# Ethernet_Sheet.net
KiCad netlist of a schematic drawn in Altium Designer
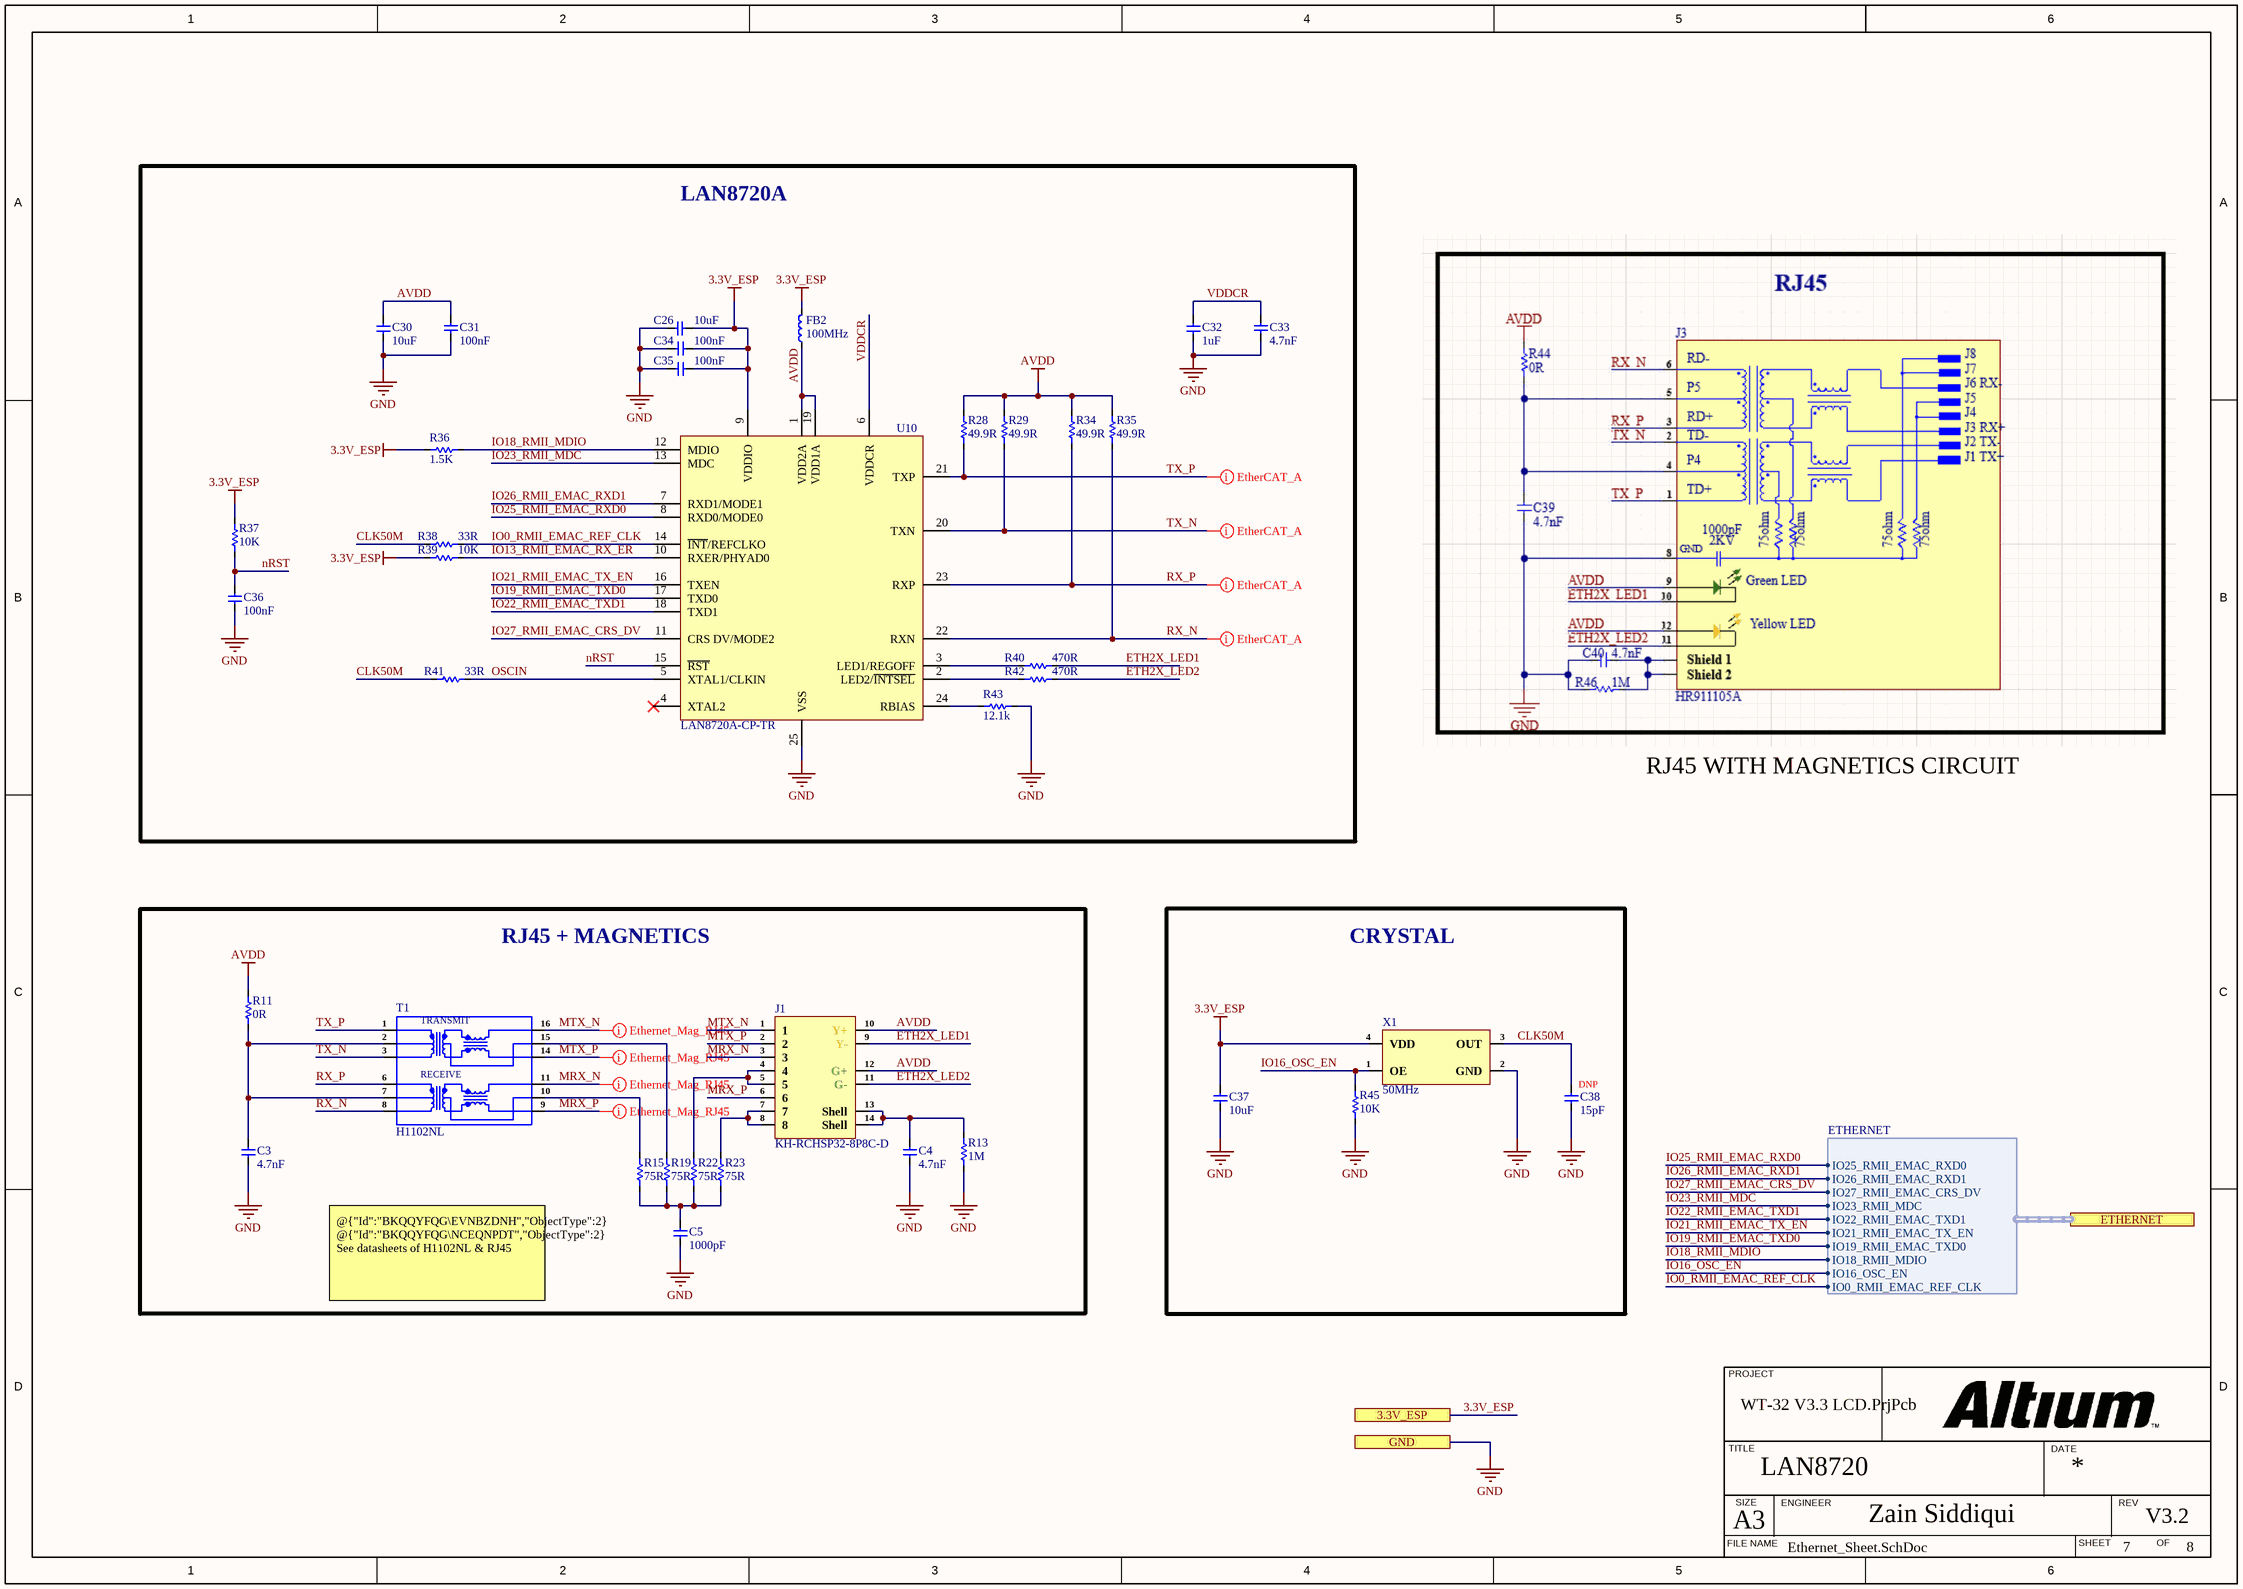
[diagram p0: Ethernet_Sheet.SchDoc]

(export (version "E")
  (design (tool "Eeschema 10.0.6"))
  (components
    (comp (ref "C3")
      (value "4.7nF")
      (footprint "Cap-0402")
      (description "CAP CER 4700PF 50V X7R 0402")
      (fields
        (field (name "MANUFACTURER") "Yageo")
        (field (name "MANUFACTURER PART NUMBER") "CC0402KRX7R9BB472")
      )
      (libsource (lib "eSpark Libraries") (part "CC0402KRX7R9BB472"))
    )
    (comp (ref "C4")
      (value "4.7nF")
      (footprint "Cap-1206")
      (description "CAP CER 4700PF 1KV X7R 1206")
      (fields
        (field (name "MANUFACTURER") "Yageo")
        (field (name "MANUFACTURER PART NUMBER") "CC1206KKX7RCBB472")
      )
      (libsource (lib "eSpark Libraries") (part "CC1206KKX7RCBB472"))
    )
    (comp (ref "C5")
      (value "1000pF")
      (footprint "Cap-1206")
      (description "CAP CER 1000PF 2KV X7R 1206")
      (fields
        (field (name "MANUFACTURER") "Yageo")
        (field (name "MANUFACTURER PART NUMBER") "CC1206KKX7RDBB102")
      )
      (libsource (lib "eSpark Libraries") (part "CC1206KKX7RDBB102"))
    )
    (comp (ref "C26")
      (value "10uF")
      (footprint "Cap-0603")
      (description "CAP CER 10UF 25V X5R 0603")
      (fields
        (field (name "MANUFACTURER") "Samsung")
        (field (name "MANUFACTURER PART NUMBER") "CL10A106MA8NRNC")
      )
      (libsource (lib "eSpark Libraries") (part "CL10A106MA8NRNC"))
    )
    (comp (ref "C30")
      (value "10uF")
      (footprint "Cap-0603")
      (description "CAP CER 10UF 25V X5R 0603")
      (fields
        (field (name "MANUFACTURER") "Samsung")
        (field (name "MANUFACTURER PART NUMBER") "CL10A106MA8NRNC")
      )
      (libsource (lib "eSpark Libraries") (part "CL10A106MA8NRNC"))
    )
    (comp (ref "C31")
      (value "100nF")
      (footprint "cap-0402")
      (description "CAP CER 0.1UF 50V X7R 0402")
      (fields
        (field (name "MANUFACTURER") "TDK")
        (field (name "MANUFACTURER PART NUMBER") "C1005X7R1H104KT000F")
      )
      (libsource (lib "eSpark Libraries") (part "C1005X7R1H104KT000F"))
    )
    (comp (ref "C32")
      (value "1uF")
      (footprint "Cap-0402")
      (description "CAP CER 1UF 16V X5R 0402")
      (fields
        (field (name "MANUFACTURER") "Yageo")
        (field (name "MANUFACTURER PART NUMBER") "CC0402KRX5R7BB105")
      )
      (libsource (lib "eSpark Libraries") (part "CC0402KRX5R7BB105"))
    )
    (comp (ref "C33")
      (value "4.7nF")
      (footprint "Cap-0402")
      (description "CAP CER 4700PF 50V X7R 0402")
      (fields
        (field (name "MANUFACTURER") "Yageo")
        (field (name "MANUFACTURER PART NUMBER") "CC0402KRX7R9BB472")
      )
      (libsource (lib "eSpark Libraries") (part "CC0402KRX7R9BB472"))
    )
    (comp (ref "C34")
      (value "100nF")
      (footprint "cap-0402")
      (description "CAP CER 0.1UF 50V X7R 0402")
      (fields
        (field (name "MANUFACTURER") "TDK")
        (field (name "MANUFACTURER PART NUMBER") "C1005X7R1H104KT000F")
      )
      (libsource (lib "eSpark Libraries") (part "C1005X7R1H104KT000F"))
    )
    (comp (ref "C35")
      (value "100nF")
      (footprint "cap-0402")
      (description "CAP CER 0.1UF 50V X7R 0402")
      (fields
        (field (name "MANUFACTURER") "TDK")
        (field (name "MANUFACTURER PART NUMBER") "C1005X7R1H104KT000F")
      )
      (libsource (lib "eSpark Libraries") (part "C1005X7R1H104KT000F"))
    )
    (comp (ref "C36")
      (value "100nF")
      (footprint "cap-0402")
      (description "CAP CER 0.1UF 50V X7R 0402")
      (fields
        (field (name "MANUFACTURER") "TDK")
        (field (name "MANUFACTURER PART NUMBER") "C1005X7R1H104KT000F")
      )
      (libsource (lib "eSpark Libraries") (part "C1005X7R1H104KT000F"))
    )
    (comp (ref "C37")
      (value "10uF")
      (footprint "Cap-0603")
      (description "CAP CER 10UF 25V X5R 0603")
      (fields
        (field (name "MANUFACTURER") "Samsung")
        (field (name "MANUFACTURER PART NUMBER") "CL10A106MA8NRNC")
      )
      (libsource (lib "eSpark Libraries") (part "CL10A106MA8NRNC"))
    )
    (comp (ref "C38")
      (value "15pF")
      (footprint "Cap-0603")
      (description "CAP CER 15PF 50V C0G/NPO 0603")
      (fields
        (field (name "MANUFACTURER") "Yageo")
        (field (name "MANUFACTURER PART NUMBER") "CC0603JRNPO9BN150")
      )
      (libsource (lib "eSpark Libraries") (part "CC0603JRNPO9BN150"))
    )
    (comp (ref "FB2")
      (value "100MHz")
      (footprint "IND-1206")
      (description "FERRITE BEAD 120 OHM 1206 1LN")
      (fields
        (field (name "MANUFACTURER") "Murata")
        (field (name "MANUFACTURER PART NUMBER") "BLM31PG121SN1L")
      )
      (libsource (lib "eSpark Libraries") (part "BLM31PG121SN1L"))
    )
    (comp (ref "J1")
      (value "KH-RCHSP32-8P8C-D")
      (footprint "KH-RCHSP32-8P8C-D")
      (description "Jack Modular Connector RJ45 Through Hole, Right Angle Shielded")
      (fields (field (name "MANUFACTURER") "kinghelm") (field (name "LCSC PART NUMBER") "C2828084"))
      (libsource (lib "eSpark Libraries") (part "KH-RCHSP32-8P8C-D"))
    )
    (comp (ref "R11")
      (value "0R")
      (footprint "Res-0402")
      (description "RES 0 OHM JUMPER 1/16W 0402")
      (fields
        (field (name "MANUFACTURER") "Yageo")
        (field (name "MANUFACTURER PART NUMBER") "RC0402FR-070RL")
      )
      (libsource (lib "eSpark Libraries") (part "RC0402FR-070RL"))
    )
    (comp (ref "R13")
      (value "1M")
      (footprint "Res-1206")
      (description "RES 1M OHM 1% 1/4W 1206")
      (fields
        (field (name "MANUFACTURER") "Yageo")
        (field (name "MANUFACTURER PART NUMBER") "RC1206FR-071ML")
      )
      (libsource (lib "eSpark Libraries") (part "RC1206FR-071ML"))
    )
    (comp (ref "R15")
      (value "75R")
      (footprint "Res-0402")
      (description "75Ω ±1% 62.5mW 0402 Thick Film Resistor")
      (fields
        (field (name "MANUFACTURER") "YAGEO")
        (field (name "MANUFACTURER PART NUMBER") "RC0402FR-0775RL")
      )
      (libsource (lib "eSpark Libraries") (part "RC0402FR-0775RL"))
    )
    (comp (ref "R19")
      (value "75R")
      (footprint "Res-0402")
      (description "75Ω ±1% 62.5mW 0402 Thick Film Resistor")
      (fields
        (field (name "MANUFACTURER") "YAGEO")
        (field (name "MANUFACTURER PART NUMBER") "RC0402FR-0775RL")
      )
      (libsource (lib "eSpark Libraries") (part "RC0402FR-0775RL"))
    )
    (comp (ref "R22")
      (value "75R")
      (footprint "Res-0402")
      (description "75Ω ±1% 62.5mW 0402 Thick Film Resistor")
      (fields
        (field (name "MANUFACTURER") "YAGEO")
        (field (name "MANUFACTURER PART NUMBER") "RC0402FR-0775RL")
      )
      (libsource (lib "eSpark Libraries") (part "RC0402FR-0775RL"))
    )
    (comp (ref "R23")
      (value "75R")
      (footprint "Res-0402")
      (description "75Ω ±1% 62.5mW 0402 Thick Film Resistor")
      (fields
        (field (name "MANUFACTURER") "YAGEO")
        (field (name "MANUFACTURER PART NUMBER") "RC0402FR-0775RL")
      )
      (libsource (lib "eSpark Libraries") (part "RC0402FR-0775RL"))
    )
    (comp (ref "R28")
      (value "49.9R")
      (footprint "Res-0402")
      (description "49.9Ω 62.5mW 50V ±100ppm/℃ Thick Film Resistor ±1% 0402 Chip Resistor - Surface Mount ROHS")
      (fields
        (field (name "MANUFACTURER") "YAGEO")
        (field (name "MANUFACTURER PART NUMBER") "RC0402FR-0749R9L")
      )
      (libsource (lib "eSpark Libraries") (part "RC0402FR-0749R9L"))
    )
    (comp (ref "R29")
      (value "49.9R")
      (footprint "Res-0402")
      (description "49.9Ω 62.5mW 50V ±100ppm/℃ Thick Film Resistor ±1% 0402 Chip Resistor - Surface Mount ROHS")
      (fields
        (field (name "MANUFACTURER") "YAGEO")
        (field (name "MANUFACTURER PART NUMBER") "RC0402FR-0749R9L")
      )
      (libsource (lib "eSpark Libraries") (part "RC0402FR-0749R9L"))
    )
    (comp (ref "R34")
      (value "49.9R")
      (footprint "Res-0402")
      (description "49.9Ω 62.5mW 50V ±100ppm/℃ Thick Film Resistor ±1% 0402 Chip Resistor - Surface Mount ROHS")
      (fields
        (field (name "MANUFACTURER") "YAGEO")
        (field (name "MANUFACTURER PART NUMBER") "RC0402FR-0749R9L")
      )
      (libsource (lib "eSpark Libraries") (part "RC0402FR-0749R9L"))
    )
    (comp (ref "R35")
      (value "49.9R")
      (footprint "Res-0402")
      (description "49.9Ω 62.5mW 50V ±100ppm/℃ Thick Film Resistor ±1% 0402 Chip Resistor - Surface Mount ROHS")
      (fields
        (field (name "MANUFACTURER") "YAGEO")
        (field (name "MANUFACTURER PART NUMBER") "RC0402FR-0749R9L")
      )
      (libsource (lib "eSpark Libraries") (part "RC0402FR-0749R9L"))
    )
    (comp (ref "R36")
      (value "1.5K")
      (footprint "Res-0402")
      (description "RES 1.5K OHM 1% 1/16W 0402")
      (fields
        (field (name "MANUFACTURER") "Yageo")
        (field (name "MANUFACTURER PART NUMBER") "RC0402FR-071K5L")
      )
      (libsource (lib "eSpark Libraries") (part "RC0402FR-071K5L"))
    )
    (comp (ref "R37")
      (value "10K")
      (footprint "Res-0402")
      (description "RES 10K OHM 1% 1/16W 0402")
      (fields
        (field (name "MANUFACTURER") "Yageo")
        (field (name "MANUFACTURER PART NUMBER") "RC0402FR-0710KL")
      )
      (libsource (lib "eSpark Libraries") (part "RC0402FR-0710KL"))
    )
    (comp (ref "R38")
      (value "33R")
      (footprint "Res-0402")
      (description "RES 33 OHM 1% 1/16W 0402")
      (fields
        (field (name "MANUFACTURER") "Yageo")
        (field (name "MANUFACTURER PART NUMBER") "RC0402FR-0733RL")
      )
      (libsource (lib "eSpark Libraries") (part "RC0402FR-0733RL"))
    )
    (comp (ref "R39")
      (value "10K")
      (footprint "Res-0402")
      (description "RES 10K OHM 1% 1/16W 0402")
      (fields
        (field (name "MANUFACTURER") "Yageo")
        (field (name "MANUFACTURER PART NUMBER") "RC0402FR-0710KL")
      )
      (libsource (lib "eSpark Libraries") (part "RC0402FR-0710KL"))
    )
    (comp (ref "R40")
      (value "470R")
      (footprint "Res-0402")
      (description "RES 470 OHM 1% 1/16W 0402")
      (fields
        (field (name "MANUFACTURER") "Yageo")
        (field (name "MANUFACTURER PART NUMBER") "RC0402FR-07470RL")
      )
      (libsource (lib "eSpark Libraries") (part "RC0402FR-07470RL"))
    )
    (comp (ref "R41")
      (value "33R")
      (footprint "Res-0402")
      (description "RES 33 OHM 1% 1/16W 0402")
      (fields
        (field (name "MANUFACTURER") "Yageo")
        (field (name "MANUFACTURER PART NUMBER") "RC0402FR-0733RL")
      )
      (libsource (lib "eSpark Libraries") (part "RC0402FR-0733RL"))
    )
    (comp (ref "R42")
      (value "470R")
      (footprint "Res-0402")
      (description "RES 470 OHM 1% 1/16W 0402")
      (fields
        (field (name "MANUFACTURER") "Yageo")
        (field (name "MANUFACTURER PART NUMBER") "RC0402FR-07470RL")
      )
      (libsource (lib "eSpark Libraries") (part "RC0402FR-07470RL"))
    )
    (comp (ref "R43")
      (value "12.1k")
      (footprint "Res-0402")
      (description "RES SMD 12.1KOHM 0.1% 1/16W 0402")
      (fields
        (field (name "MANUFACTURER") "Yageo")
        (field (name "MANUFACTURER PART NUMBER") "RT0402BRD0712K1L")
      )
      (libsource (lib "eSpark Libraries") (part "RT0402BRD0712K1L"))
    )
    (comp (ref "R45")
      (value "10K")
      (footprint "Res-0402")
      (description "RES 10K OHM 1% 1/16W 0402")
      (fields
        (field (name "MANUFACTURER") "Yageo")
        (field (name "MANUFACTURER PART NUMBER") "RC0402FR-0710KL")
      )
      (libsource (lib "eSpark Libraries") (part "RC0402FR-0710KL"))
    )
    (comp (ref "T1")
      (value "H1102NL")
      (footprint "H1102NLT")
      (description "XFRMR MAGNETIC 1PORT 1:1 10/100")
      (fields (field (name "MANUFACTURER") "Pulse") (field (name "LCSC PART NUMBER") "C18584"))
      (libsource (lib "eSpark Libraries") (part "H1102NL"))
    )
    (comp (ref "U10")
      (value "LAN8720A-CP-TR")
      (footprint "LAN8720A-CP-TR")
      (description "IC TRANSCEIVER FULL 2/2 24SQFN")
      (fields (field (name "MANUFACTURER") "MICROCHIP") (field (name "LCSC PART NUMBER") "C45223"))
      (libsource (lib "eSpark Libraries") (part "LAN8720A-CP-TR"))
    )
    (comp (ref "X1")
      (value "50MHz")
      (footprint "OT2EL4C4JI-111OLP-50M")
      (description "1.8V~3.3V ±10ppm ±20ppm CMOS 50MHz SMD3225-4P Crystal Oscillators ROHS")
      (fields
        (field (name "MANUFACTURER") "YXC Crystal Oscillators")
        (field (name "MANUFACTURER PART NUMBER") "OT2EL4C4JI-111OLP-50M")
      )
      (libsource (lib "eSpark Libraries") (part "OT2EL4C4JI-111OLP-50M"))
    )
  )
  (nets
    (net (code "2") (name "/CLK50M") (class "Default")
      (node (ref "C38") (pin "2") (pinfunction "2_2") (pintype "passive"))
      (node (ref "R38") (pin "1") (pinfunction "1_1") (pintype "passive"))
      (node (ref "R41") (pin "1") (pinfunction "1_1") (pintype "passive"))
      (node (ref "X1") (pin "3") (pinfunction "OUT_3") (pintype "passive"))
    )
    (net (code "3") (name "/ETH2X_LED1") (class "Default")
      (node (ref "J1") (pin "9") (pinfunction "Y-_9") (pintype "passive"))
      (node (ref "R40") (pin "2") (pinfunction "2_2") (pintype "passive"))
    )
    (net (code "4") (name "/ETH2X_LED2") (class "Default")
      (node (ref "J1") (pin "11") (pinfunction "G-_11") (pintype "passive"))
      (node (ref "R42") (pin "2") (pinfunction "2_2") (pintype "passive"))
    )
    (net (code "5") (name "/IO0_RMII_EMAC_REF_CLK") (class "Default")
      (node (ref "R38") (pin "2") (pinfunction "2_2") (pintype "passive"))
      (node (ref "U10") (pin "14") (pinfunction "~{INT}/REFCLKO_14") (pintype "passive"))
    )
    (net (code "6") (name "/IO13_RMII_EMAC_RX_ER") (class "Default")
      (node (ref "R39") (pin "1") (pinfunction "1_1") (pintype "passive"))
      (node (ref "U10") (pin "10") (pinfunction "RXER/PHYAD0_10") (pintype "passive"))
    )
    (net (code "7") (name "/IO16_OSC_EN") (class "Default")
      (node (ref "R45") (pin "1") (pinfunction "1_1") (pintype "passive"))
      (node (ref "X1") (pin "1") (pinfunction "OE_1") (pintype "passive"))
    )
    (net (code "8") (name "/IO18_RMII_MDIO") (class "Default")
      (node (ref "R36") (pin "1") (pinfunction "1_1") (pintype "passive"))
      (node (ref "U10") (pin "12") (pinfunction "MDIO_12") (pintype "passive"))
    )
    (net (code "9") (name "/IO19_RMII_EMAC_TXD0") (class "Default")
      (node (ref "U10") (pin "17") (pinfunction "TXD0_17") (pintype "passive"))
    )
    (net (code "10") (name "/IO21_RMII_EMAC_TX_EN") (class "Default")
      (node (ref "U10") (pin "16") (pinfunction "TXEN_16") (pintype "passive"))
    )
    (net (code "11") (name "/IO22_RMII_EMAC_TXD1") (class "Default")
      (node (ref "U10") (pin "18") (pinfunction "TXD1_18") (pintype "passive"))
    )
    (net (code "12") (name "/IO23_RMII_MDC") (class "Default")
      (node (ref "U10") (pin "13") (pinfunction "MDC_13") (pintype "passive"))
    )
    (net (code "13") (name "/IO25_RMII_EMAC_RXD0") (class "Default")
      (node (ref "U10") (pin "8") (pinfunction "RXD0/MODE0_8") (pintype "passive"))
    )
    (net (code "14") (name "/IO26_RMII_EMAC_RXD1") (class "Default")
      (node (ref "U10") (pin "7") (pinfunction "RXD1/MODE1_7") (pintype "passive"))
    )
    (net (code "15") (name "/IO27_RMII_EMAC_CRS_DV") (class "Default")
      (node (ref "U10") (pin "11") (pinfunction "CRS_DV/MODE2_11") (pintype "passive"))
    )
    (net (code "16") (name "/MRX_N") (class "Default")
      (node (ref "J1") (pin "3") (pinfunction "3_3") (pintype "passive"))
      (node (ref "T1") (pin "11") (pinfunction "11_11") (pintype "passive"))
    )
    (net (code "17") (name "/MRX_P") (class "Default")
      (node (ref "J1") (pin "6") (pinfunction "6_6") (pintype "passive"))
      (node (ref "T1") (pin "9") (pinfunction "9_9") (pintype "passive"))
    )
    (net (code "18") (name "/MTX_N") (class "Default")
      (node (ref "J1") (pin "1") (pinfunction "1_1") (pintype "passive"))
      (node (ref "T1") (pin "16") (pinfunction "16_16") (pintype "passive"))
    )
    (net (code "19") (name "/MTX_P") (class "Default")
      (node (ref "J1") (pin "2") (pinfunction "2_2") (pintype "passive"))
      (node (ref "T1") (pin "14") (pinfunction "14_14") (pintype "passive"))
    )
    (net (code "20") (name "/OSCIN") (class "Default")
      (node (ref "R41") (pin "2") (pinfunction "2_2") (pintype "passive"))
      (node (ref "U10") (pin "5") (pinfunction "XTAL1/CLKIN_5") (pintype "passive"))
    )
    (net (code "21") (name "/RX_N") (class "Default")
      (node (ref "R35") (pin "1") (pinfunction "1_1") (pintype "passive"))
      (node (ref "T1") (pin "8") (pinfunction "8_8") (pintype "passive"))
      (node (ref "U10") (pin "22") (pinfunction "RXN_22") (pintype "passive"))
    )
    (net (code "22") (name "/RX_P") (class "Default")
      (node (ref "R34") (pin "1") (pinfunction "1_1") (pintype "passive"))
      (node (ref "T1") (pin "6") (pinfunction "6_6") (pintype "passive"))
      (node (ref "U10") (pin "23") (pinfunction "RXP_23") (pintype "passive"))
    )
    (net (code "23") (name "/TX_N") (class "Default")
      (node (ref "R29") (pin "1") (pinfunction "1_1") (pintype "passive"))
      (node (ref "T1") (pin "3") (pinfunction "3_3") (pintype "passive"))
      (node (ref "U10") (pin "20") (pinfunction "TXN_20") (pintype "passive"))
    )
    (net (code "24") (name "/TX_P") (class "Default")
      (node (ref "R28") (pin "1") (pinfunction "1_1") (pintype "passive"))
      (node (ref "T1") (pin "1") (pinfunction "1_1") (pintype "passive"))
      (node (ref "U10") (pin "21") (pinfunction "TXP_21") (pintype "passive"))
    )
    (net (code "25") (name "/VDDCR") (class "Default")
      (node (ref "C32") (pin "2") (pinfunction "2_2") (pintype "passive"))
      (node (ref "C33") (pin "1") (pinfunction "1_1") (pintype "passive"))
      (node (ref "U10") (pin "6") (pinfunction "VDDCR_6") (pintype "passive"))
    )
    (net (code "26") (name "/nRST") (class "Default")
      (node (ref "C36") (pin "2") (pinfunction "2_2") (pintype "passive"))
      (node (ref "R37") (pin "1") (pinfunction "1_1") (pintype "passive"))
      (node (ref "U10") (pin "15") (pinfunction "~{RST}_15") (pintype "passive"))
    )
    (net (code "28") (name "3.3V_ESP") (class "Default")
      (node (ref "C26") (pin "2") (pinfunction "2_2") (pintype "passive"))
      (node (ref "C34") (pin "1") (pinfunction "1_1") (pintype "passive"))
      (node (ref "C35") (pin "1") (pinfunction "1_1") (pintype "passive"))
      (node (ref "C37") (pin "2") (pinfunction "2_2") (pintype "passive"))
      (node (ref "FB2") (pin "2") (pinfunction "2_2") (pintype "passive"))
      (node (ref "R36") (pin "2") (pinfunction "2_2") (pintype "passive"))
      (node (ref "R37") (pin "2") (pinfunction "2_2") (pintype "passive"))
      (node (ref "R39") (pin "2") (pinfunction "2_2") (pintype "passive"))
      (node (ref "U10") (pin "9") (pinfunction "VDDIO_9") (pintype "passive"))
      (node (ref "X1") (pin "4") (pinfunction "VDD_4") (pintype "passive"))
    )
    (net (code "29") (name "AVDD") (class "Default")
      (node (ref "C30") (pin "2") (pinfunction "2_2") (pintype "passive"))
      (node (ref "C31") (pin "1") (pinfunction "1_1") (pintype "passive"))
      (node (ref "FB2") (pin "1") (pinfunction "1_1") (pintype "passive"))
      (node (ref "J1") (pin "10") (pinfunction "Y+_10") (pintype "passive"))
      (node (ref "J1") (pin "12") (pinfunction "G+_12") (pintype "passive"))
      (node (ref "R11") (pin "2") (pinfunction "2_2") (pintype "passive"))
      (node (ref "R28") (pin "2") (pinfunction "2_2") (pintype "passive"))
      (node (ref "R29") (pin "2") (pinfunction "2_2") (pintype "passive"))
      (node (ref "R34") (pin "2") (pinfunction "2_2") (pintype "passive"))
      (node (ref "R35") (pin "2") (pinfunction "2_2") (pintype "passive"))
      (node (ref "U10") (pin "1") (pinfunction "VDD2A_1") (pintype "passive"))
      (node (ref "U10") (pin "19") (pinfunction "VDD1A_19") (pintype "passive"))
    )
    (net (code "30") (name "GND") (class "Default")
      (node (ref "C26") (pin "1") (pinfunction "1_1") (pintype "passive"))
      (node (ref "C3") (pin "1") (pinfunction "1_1") (pintype "passive"))
      (node (ref "C30") (pin "1") (pinfunction "1_1") (pintype "passive"))
      (node (ref "C31") (pin "2") (pinfunction "2_2") (pintype "passive"))
      (node (ref "C32") (pin "1") (pinfunction "1_1") (pintype "passive"))
      (node (ref "C33") (pin "2") (pinfunction "2_2") (pintype "passive"))
      (node (ref "C34") (pin "2") (pinfunction "2_2") (pintype "passive"))
      (node (ref "C35") (pin "2") (pinfunction "2_2") (pintype "passive"))
      (node (ref "C36") (pin "1") (pinfunction "1_1") (pintype "passive"))
      (node (ref "C37") (pin "1") (pinfunction "1_1") (pintype "passive"))
      (node (ref "C38") (pin "1") (pinfunction "1_1") (pintype "passive"))
      (node (ref "C4") (pin "1") (pinfunction "1_1") (pintype "passive"))
      (node (ref "C5") (pin "1") (pinfunction "1_1") (pintype "passive"))
      (node (ref "R13") (pin "1") (pinfunction "1_1") (pintype "passive"))
      (node (ref "R43") (pin "1") (pinfunction "1_1") (pintype "passive"))
      (node (ref "R45") (pin "2") (pinfunction "2_2") (pintype "passive"))
      (node (ref "U10") (pin "25") (pinfunction "VSS_25") (pintype "passive"))
      (node (ref "X1") (pin "2") (pinfunction "GND_2") (pintype "passive"))
    )
    (net (code "31") (name "Net-(C3-Pad2)") (class "Default")
      (node (ref "C3") (pin "2") (pinfunction "2_2") (pintype "passive"))
      (node (ref "R11") (pin "1") (pinfunction "1_1") (pintype "passive"))
      (node (ref "T1") (pin "2") (pinfunction "2_2") (pintype "passive"))
      (node (ref "T1") (pin "7") (pinfunction "7_7") (pintype "passive"))
    )
    (net (code "32") (name "Net-(C4-Pad2)") (class "Default")
      (node (ref "C4") (pin "2") (pinfunction "2_2") (pintype "passive"))
      (node (ref "J1") (pin "13") (pinfunction "Shell_13") (pintype "passive"))
      (node (ref "J1") (pin "14") (pinfunction "Shell_14") (pintype "passive"))
      (node (ref "R13") (pin "2") (pinfunction "2_2") (pintype "passive"))
    )
    (net (code "33") (name "Net-(C5-Pad2)") (class "Default")
      (node (ref "C5") (pin "2") (pinfunction "2_2") (pintype "passive"))
      (node (ref "R15") (pin "2") (pinfunction "2_2") (pintype "passive"))
      (node (ref "R19") (pin "2") (pinfunction "2_2") (pintype "passive"))
      (node (ref "R22") (pin "2") (pinfunction "2_2") (pintype "passive"))
      (node (ref "R23") (pin "2") (pinfunction "2_2") (pintype "passive"))
    )
    (net (code "34") (name "Net-(J1-Pad4)") (class "Default")
      (node (ref "J1") (pin "4") (pinfunction "4_4") (pintype "passive"))
      (node (ref "J1") (pin "5") (pinfunction "5_5") (pintype "passive"))
      (node (ref "R22") (pin "1") (pinfunction "1_1") (pintype "passive"))
    )
    (net (code "35") (name "Net-(J1-Pad7)") (class "Default")
      (node (ref "J1") (pin "7") (pinfunction "7_7") (pintype "passive"))
      (node (ref "J1") (pin "8") (pinfunction "8_8") (pintype "passive"))
      (node (ref "R23") (pin "1") (pinfunction "1_1") (pintype "passive"))
    )
    (net (code "36") (name "Net-(R15-Pad1)") (class "Default")
      (node (ref "R15") (pin "1") (pinfunction "1_1") (pintype "passive"))
      (node (ref "T1") (pin "10") (pinfunction "10_10") (pintype "passive"))
    )
    (net (code "37") (name "Net-(R19-Pad1)") (class "Default")
      (node (ref "R19") (pin "1") (pinfunction "1_1") (pintype "passive"))
      (node (ref "T1") (pin "15") (pinfunction "15_15") (pintype "passive"))
    )
    (net (code "38") (name "Net-(U10-LED1{slash}REGOFF)") (class "Default")
      (node (ref "R40") (pin "1") (pinfunction "1_1") (pintype "passive"))
      (node (ref "U10") (pin "3") (pinfunction "LED1/REGOFF_3") (pintype "passive"))
    )
    (net (code "39") (name "Net-(U10-LED2{slash}~{INTSEL})") (class "Default")
      (node (ref "R42") (pin "1") (pinfunction "1_1") (pintype "passive"))
      (node (ref "U10") (pin "2") (pinfunction "LED2/~{INTSEL}_2") (pintype "passive"))
    )
    (net (code "40") (name "Net-(U10-RBIAS)") (class "Default")
      (node (ref "R43") (pin "2") (pinfunction "2_2") (pintype "passive"))
      (node (ref "U10") (pin "24") (pinfunction "RBIAS_24") (pintype "passive"))
    )
    (net (code "41") (name "unconnected-(U10-XTAL2-Pad4)") (class "Default")
      (node (ref "U10") (pin "4") (pinfunction "XTAL2_4") (pintype "passive+no_connect"))
    )
  )
)
